# HVGA.net
KiCad netlist of a schematic drawn in Altium Designer
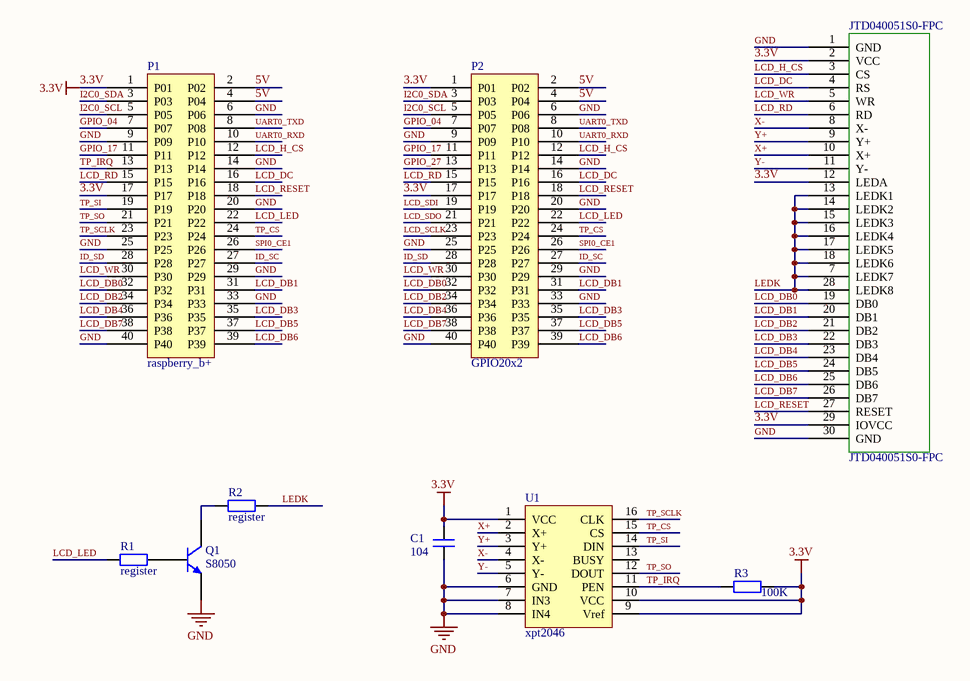
[diagram p0: HVGA.SchDoc]

(export (version "E")
  (design (tool "Eeschema 10.0.6"))
  (components
    (comp (ref "C1") (value "104") (footprint "1206") (libsource (lib "4.0_30P原理图库") (part "capacitor")))
    (comp (ref "JTD040051S0-FPC")
      (value "JTD040051S0-FPC")
      (footprint "JTD040051S0-FPC")
      (libsource (lib "4.0_30P原理图库") (part "JTD040051S0-FPC"))
    )
    (comp (ref "P1")
      (value "raspberry_b+")
      (footprint "GPIO20x2")
      (libsource (lib "4.0_30P原理图库") (part "raspberry_b+"))
    )
    (comp (ref "P2")
      (value "GPIO20x2")
      (footprint "GPIO20x2")
      (libsource (lib "4.0_30P原理图库") (part "raspberry_b+"))
    )
    (comp (ref "Q1") (value "S8050") (footprint "SOT23") (libsource (lib "4.0_30P原理图库") (part "S8050")))
    (comp (ref "R1") (value "register") (footprint "1206") (libsource (lib "4.0_30P原理图库") (part "register")))
    (comp (ref "R2") (value "register") (footprint "1206") (libsource (lib "4.0_30P原理图库") (part "register")))
    (comp (ref "R3") (value "100K") (footprint "1206") (libsource (lib "4.0_30P原理图库") (part "register")))
    (comp (ref "U1") (value "xpt2046") (footprint "TSSOP16") (libsource (lib "4.0_30P原理图库") (part "xpt2046")))
  )
  (nets
    (net (code "1") (name "/5V") (class "Default")
      (node (ref "P1") (pin "2") (pinfunction "P02_2") (pintype "passive"))
      (node (ref "P1") (pin "4") (pinfunction "P04_4") (pintype "passive"))
      (node (ref "P2") (pin "2") (pinfunction "P02_2") (pintype "passive"))
      (node (ref "P2") (pin "4") (pinfunction "P04_4") (pintype "passive"))
    )
    (net (code "2") (name "/GPIO_04") (class "Default")
      (node (ref "P1") (pin "7") (pinfunction "P07_7") (pintype "passive"))
      (node (ref "P2") (pin "7") (pinfunction "P07_7") (pintype "passive"))
    )
    (net (code "3") (name "/GPIO_17") (class "Default")
      (node (ref "P1") (pin "11") (pinfunction "P11_11") (pintype "passive"))
      (node (ref "P2") (pin "11") (pinfunction "P11_11") (pintype "passive"))
    )
    (net (code "4") (name "/GPIO_27") (class "Default")
      (node (ref "P2") (pin "13") (pinfunction "P13_13") (pintype "passive"))
    )
    (net (code "5") (name "/I2C0_SCL") (class "Default")
      (node (ref "P1") (pin "5") (pinfunction "P05_5") (pintype "passive"))
      (node (ref "P2") (pin "5") (pinfunction "P05_5") (pintype "passive"))
    )
    (net (code "6") (name "/I2C0_SDA") (class "Default")
      (node (ref "P1") (pin "3") (pinfunction "P03_3") (pintype "passive"))
      (node (ref "P2") (pin "3") (pinfunction "P03_3") (pintype "passive"))
    )
    (net (code "7") (name "/ID_SC") (class "Default")
      (node (ref "P1") (pin "27") (pinfunction "P27_27") (pintype "passive"))
      (node (ref "P2") (pin "27") (pinfunction "P27_27") (pintype "passive"))
    )
    (net (code "8") (name "/ID_SD") (class "Default")
      (node (ref "P1") (pin "28") (pinfunction "P28_28") (pintype "passive"))
      (node (ref "P2") (pin "28") (pinfunction "P28_28") (pintype "passive"))
    )
    (net (code "9") (name "/LCD_DB0") (class "Default")
      (node (ref "JTD040051S0-FPC") (pin "19") (pinfunction "DB0_19") (pintype "passive"))
      (node (ref "P1") (pin "32") (pinfunction "P32_32") (pintype "passive"))
      (node (ref "P2") (pin "32") (pinfunction "P32_32") (pintype "passive"))
    )
    (net (code "10") (name "/LCD_DB1") (class "Default")
      (node (ref "JTD040051S0-FPC") (pin "20") (pinfunction "DB1_20") (pintype "passive"))
      (node (ref "P1") (pin "31") (pinfunction "P31_31") (pintype "passive"))
      (node (ref "P2") (pin "31") (pinfunction "P31_31") (pintype "passive"))
    )
    (net (code "11") (name "/LCD_DB2") (class "Default")
      (node (ref "JTD040051S0-FPC") (pin "21") (pinfunction "DB2_21") (pintype "passive"))
      (node (ref "P1") (pin "34") (pinfunction "P34_34") (pintype "passive"))
      (node (ref "P2") (pin "34") (pinfunction "P34_34") (pintype "passive"))
    )
    (net (code "12") (name "/LCD_DB3") (class "Default")
      (node (ref "JTD040051S0-FPC") (pin "22") (pinfunction "DB3_22") (pintype "passive"))
      (node (ref "P1") (pin "35") (pinfunction "P35_35") (pintype "passive"))
      (node (ref "P2") (pin "35") (pinfunction "P35_35") (pintype "passive"))
    )
    (net (code "13") (name "/LCD_DB4") (class "Default")
      (node (ref "JTD040051S0-FPC") (pin "23") (pinfunction "DB4_23") (pintype "passive"))
      (node (ref "P1") (pin "36") (pinfunction "P36_36") (pintype "passive"))
      (node (ref "P2") (pin "36") (pinfunction "P36_36") (pintype "passive"))
    )
    (net (code "14") (name "/LCD_DB5") (class "Default")
      (node (ref "JTD040051S0-FPC") (pin "24") (pinfunction "DB5_24") (pintype "passive"))
      (node (ref "P1") (pin "37") (pinfunction "P37_37") (pintype "passive"))
      (node (ref "P2") (pin "37") (pinfunction "P37_37") (pintype "passive"))
    )
    (net (code "15") (name "/LCD_DB6") (class "Default")
      (node (ref "JTD040051S0-FPC") (pin "25") (pinfunction "DB6_25") (pintype "passive"))
      (node (ref "P1") (pin "39") (pinfunction "P39_39") (pintype "passive"))
      (node (ref "P2") (pin "39") (pinfunction "P39_39") (pintype "passive"))
    )
    (net (code "16") (name "/LCD_DB7") (class "Default")
      (node (ref "JTD040051S0-FPC") (pin "26") (pinfunction "DB7_26") (pintype "passive"))
      (node (ref "P1") (pin "38") (pinfunction "P38_38") (pintype "passive"))
      (node (ref "P2") (pin "38") (pinfunction "P38_38") (pintype "passive"))
    )
    (net (code "17") (name "/LCD_DC") (class "Default")
      (node (ref "JTD040051S0-FPC") (pin "4") (pinfunction "RS_4") (pintype "passive"))
      (node (ref "P1") (pin "16") (pinfunction "P16_16") (pintype "passive"))
      (node (ref "P2") (pin "16") (pinfunction "P16_16") (pintype "passive"))
    )
    (net (code "18") (name "/LCD_H_CS") (class "Default")
      (node (ref "JTD040051S0-FPC") (pin "3") (pinfunction "CS_3") (pintype "passive"))
      (node (ref "P1") (pin "12") (pinfunction "P12_12") (pintype "passive"))
      (node (ref "P2") (pin "12") (pinfunction "P12_12") (pintype "passive"))
    )
    (net (code "19") (name "/LCD_LED") (class "Default")
      (node (ref "P1") (pin "22") (pinfunction "P22_22") (pintype "passive"))
      (node (ref "P2") (pin "22") (pinfunction "P22_22") (pintype "passive"))
      (node (ref "R1") (pin "1") (pinfunction "1_1") (pintype "passive"))
    )
    (net (code "20") (name "/LCD_RD") (class "Default")
      (node (ref "JTD040051S0-FPC") (pin "6") (pinfunction "RD_6") (pintype "passive"))
      (node (ref "P1") (pin "15") (pinfunction "P15_15") (pintype "passive"))
      (node (ref "P2") (pin "15") (pinfunction "P15_15") (pintype "passive"))
    )
    (net (code "21") (name "/LCD_RESET") (class "Default")
      (node (ref "JTD040051S0-FPC") (pin "27") (pinfunction "RESET_27") (pintype "passive"))
      (node (ref "P1") (pin "18") (pinfunction "P18_18") (pintype "passive"))
      (node (ref "P2") (pin "18") (pinfunction "P18_18") (pintype "passive"))
    )
    (net (code "22") (name "/LCD_SCLK") (class "Default")
      (node (ref "P2") (pin "23") (pinfunction "P23_23") (pintype "passive"))
    )
    (net (code "23") (name "/LCD_SDI") (class "Default")
      (node (ref "P2") (pin "19") (pinfunction "P19_19") (pintype "passive"))
    )
    (net (code "24") (name "/LCD_SDO") (class "Default")
      (node (ref "P2") (pin "21") (pinfunction "P21_21") (pintype "passive"))
    )
    (net (code "25") (name "/LCD_WR") (class "Default")
      (node (ref "JTD040051S0-FPC") (pin "5") (pinfunction "WR_5") (pintype "passive"))
      (node (ref "P1") (pin "30") (pinfunction "P30_30") (pintype "passive"))
      (node (ref "P2") (pin "30") (pinfunction "P30_30") (pintype "passive"))
    )
    (net (code "26") (name "/LEDK") (class "Default")
      (node (ref "JTD040051S0-FPC") (pin "13") (pinfunction "LEDK1_13") (pintype "passive"))
      (node (ref "JTD040051S0-FPC") (pin "14") (pinfunction "LEDK2_14") (pintype "passive"))
      (node (ref "JTD040051S0-FPC") (pin "15") (pinfunction "LEDK3_15") (pintype "passive"))
      (node (ref "JTD040051S0-FPC") (pin "16") (pinfunction "LEDK4_16") (pintype "passive"))
      (node (ref "JTD040051S0-FPC") (pin "17") (pinfunction "LEDK5_17") (pintype "passive"))
      (node (ref "JTD040051S0-FPC") (pin "18") (pinfunction "LEDK6_18") (pintype "passive"))
      (node (ref "JTD040051S0-FPC") (pin "28") (pinfunction "LEDK8_28") (pintype "passive"))
      (node (ref "JTD040051S0-FPC") (pin "7") (pinfunction "LEDK7_7") (pintype "passive"))
      (node (ref "R2") (pin "2") (pinfunction "2_2") (pintype "passive"))
    )
    (net (code "27") (name "/SPI0_CE1") (class "Default")
      (node (ref "P1") (pin "26") (pinfunction "P26_26") (pintype "passive"))
      (node (ref "P2") (pin "26") (pinfunction "P26_26") (pintype "passive"))
    )
    (net (code "28") (name "/TP_CS") (class "Default")
      (node (ref "P1") (pin "24") (pinfunction "P24_24") (pintype "passive"))
      (node (ref "P2") (pin "24") (pinfunction "P24_24") (pintype "passive"))
      (node (ref "U1") (pin "15") (pinfunction "CS_15") (pintype "passive"))
    )
    (net (code "29") (name "/TP_IRQ") (class "Default")
      (node (ref "P1") (pin "13") (pinfunction "P13_13") (pintype "passive"))
      (node (ref "R3") (pin "1") (pinfunction "1_1") (pintype "passive"))
      (node (ref "U1") (pin "11") (pinfunction "PEN_11") (pintype "passive"))
    )
    (net (code "30") (name "/TP_SCLK") (class "Default")
      (node (ref "P1") (pin "23") (pinfunction "P23_23") (pintype "passive"))
      (node (ref "U1") (pin "16") (pinfunction "CLK_16") (pintype "passive"))
    )
    (net (code "31") (name "/TP_SI") (class "Default")
      (node (ref "P1") (pin "19") (pinfunction "P19_19") (pintype "passive"))
      (node (ref "U1") (pin "14") (pinfunction "DIN_14") (pintype "passive"))
    )
    (net (code "32") (name "/TP_SO") (class "Default")
      (node (ref "P1") (pin "21") (pinfunction "P21_21") (pintype "passive"))
      (node (ref "U1") (pin "12") (pinfunction "DOUT_12") (pintype "passive"))
    )
    (net (code "33") (name "/UART0_RXD") (class "Default")
      (node (ref "P1") (pin "10") (pinfunction "P10_10") (pintype "passive"))
      (node (ref "P2") (pin "10") (pinfunction "P10_10") (pintype "passive"))
    )
    (net (code "34") (name "/UART0_TXD") (class "Default")
      (node (ref "P1") (pin "8") (pinfunction "P08_8") (pintype "passive"))
      (node (ref "P2") (pin "8") (pinfunction "P08_8") (pintype "passive"))
    )
    (net (code "35") (name "/X+") (class "Default")
      (node (ref "JTD040051S0-FPC") (pin "10") (pinfunction "X+_10") (pintype "passive"))
      (node (ref "U1") (pin "2") (pinfunction "X+_2") (pintype "passive"))
    )
    (net (code "36") (name "/X-") (class "Default")
      (node (ref "JTD040051S0-FPC") (pin "8") (pinfunction "X-_8") (pintype "passive"))
      (node (ref "U1") (pin "4") (pinfunction "X-_4") (pintype "passive"))
    )
    (net (code "37") (name "/Y+") (class "Default")
      (node (ref "JTD040051S0-FPC") (pin "9") (pinfunction "Y+_9") (pintype "passive"))
      (node (ref "U1") (pin "3") (pinfunction "Y+_3") (pintype "passive"))
    )
    (net (code "38") (name "/Y-") (class "Default")
      (node (ref "JTD040051S0-FPC") (pin "11") (pinfunction "Y-_11") (pintype "passive"))
      (node (ref "U1") (pin "5") (pinfunction "Y-_5") (pintype "passive"))
    )
    (net (code "39") (name "3.3V") (class "Default")
      (node (ref "C1") (pin "2") (pinfunction "2_2") (pintype "passive"))
      (node (ref "JTD040051S0-FPC") (pin "12") (pinfunction "LEDA_12") (pintype "passive"))
      (node (ref "JTD040051S0-FPC") (pin "2") (pinfunction "VCC_2") (pintype "passive"))
      (node (ref "JTD040051S0-FPC") (pin "29") (pinfunction "IOVCC_29") (pintype "passive"))
      (node (ref "P1") (pin "1") (pinfunction "P01_1") (pintype "passive"))
      (node (ref "P1") (pin "17") (pinfunction "P17_17") (pintype "passive"))
      (node (ref "P2") (pin "1") (pinfunction "P01_1") (pintype "passive"))
      (node (ref "P2") (pin "17") (pinfunction "P17_17") (pintype "passive"))
      (node (ref "R3") (pin "2") (pinfunction "2_2") (pintype "passive"))
      (node (ref "U1") (pin "1") (pinfunction "VCC_1") (pintype "passive"))
      (node (ref "U1") (pin "10") (pinfunction "VCC_10") (pintype "passive"))
      (node (ref "U1") (pin "9") (pinfunction "Vref_9") (pintype "passive"))
    )
    (net (code "40") (name "GND") (class "Default")
      (node (ref "C1") (pin "1") (pinfunction "1_1") (pintype "passive"))
      (node (ref "JTD040051S0-FPC") (pin "1") (pinfunction "GND_1") (pintype "passive"))
      (node (ref "JTD040051S0-FPC") (pin "30") (pinfunction "GND_30") (pintype "passive"))
      (node (ref "P1") (pin "14") (pinfunction "P14_14") (pintype "passive"))
      (node (ref "P1") (pin "20") (pinfunction "P20_20") (pintype "passive"))
      (node (ref "P1") (pin "25") (pinfunction "P25_25") (pintype "passive"))
      (node (ref "P1") (pin "29") (pinfunction "P29_29") (pintype "passive"))
      (node (ref "P1") (pin "33") (pinfunction "P33_33") (pintype "passive"))
      (node (ref "P1") (pin "40") (pinfunction "P40_40") (pintype "passive"))
      (node (ref "P1") (pin "6") (pinfunction "P06_6") (pintype "passive"))
      (node (ref "P1") (pin "9") (pinfunction "P09_9") (pintype "passive"))
      (node (ref "P2") (pin "14") (pinfunction "P14_14") (pintype "passive"))
      (node (ref "P2") (pin "20") (pinfunction "P20_20") (pintype "passive"))
      (node (ref "P2") (pin "25") (pinfunction "P25_25") (pintype "passive"))
      (node (ref "P2") (pin "29") (pinfunction "P29_29") (pintype "passive"))
      (node (ref "P2") (pin "33") (pinfunction "P33_33") (pintype "passive"))
      (node (ref "P2") (pin "40") (pinfunction "P40_40") (pintype "passive"))
      (node (ref "P2") (pin "6") (pinfunction "P06_6") (pintype "passive"))
      (node (ref "P2") (pin "9") (pinfunction "P09_9") (pintype "passive"))
      (node (ref "Q1") (pin "1") (pinfunction "E_1") (pintype "passive"))
      (node (ref "U1") (pin "6") (pinfunction "GND_6") (pintype "passive"))
      (node (ref "U1") (pin "7") (pinfunction "IN3_7") (pintype "passive"))
      (node (ref "U1") (pin "8") (pinfunction "IN4_8") (pintype "passive"))
    )
    (net (code "41") (name "Net-(Q1-B)") (class "Default")
      (node (ref "Q1") (pin "2") (pinfunction "B_2") (pintype "passive"))
      (node (ref "R1") (pin "2") (pinfunction "2_2") (pintype "passive"))
    )
    (net (code "42") (name "Net-(Q1-C)") (class "Default")
      (node (ref "Q1") (pin "3") (pinfunction "C_3") (pintype "passive"))
      (node (ref "R2") (pin "1") (pinfunction "1_1") (pintype "passive"))
    )
    (net (code "43") (name "unconnected-(U1-BUSY-Pad13)") (class "Default")
      (node (ref "U1") (pin "13") (pinfunction "BUSY_13") (pintype "passive"))
    )
  )
)
